# AnalogInput.net
KiCad netlist of a schematic drawn in Altium Designer
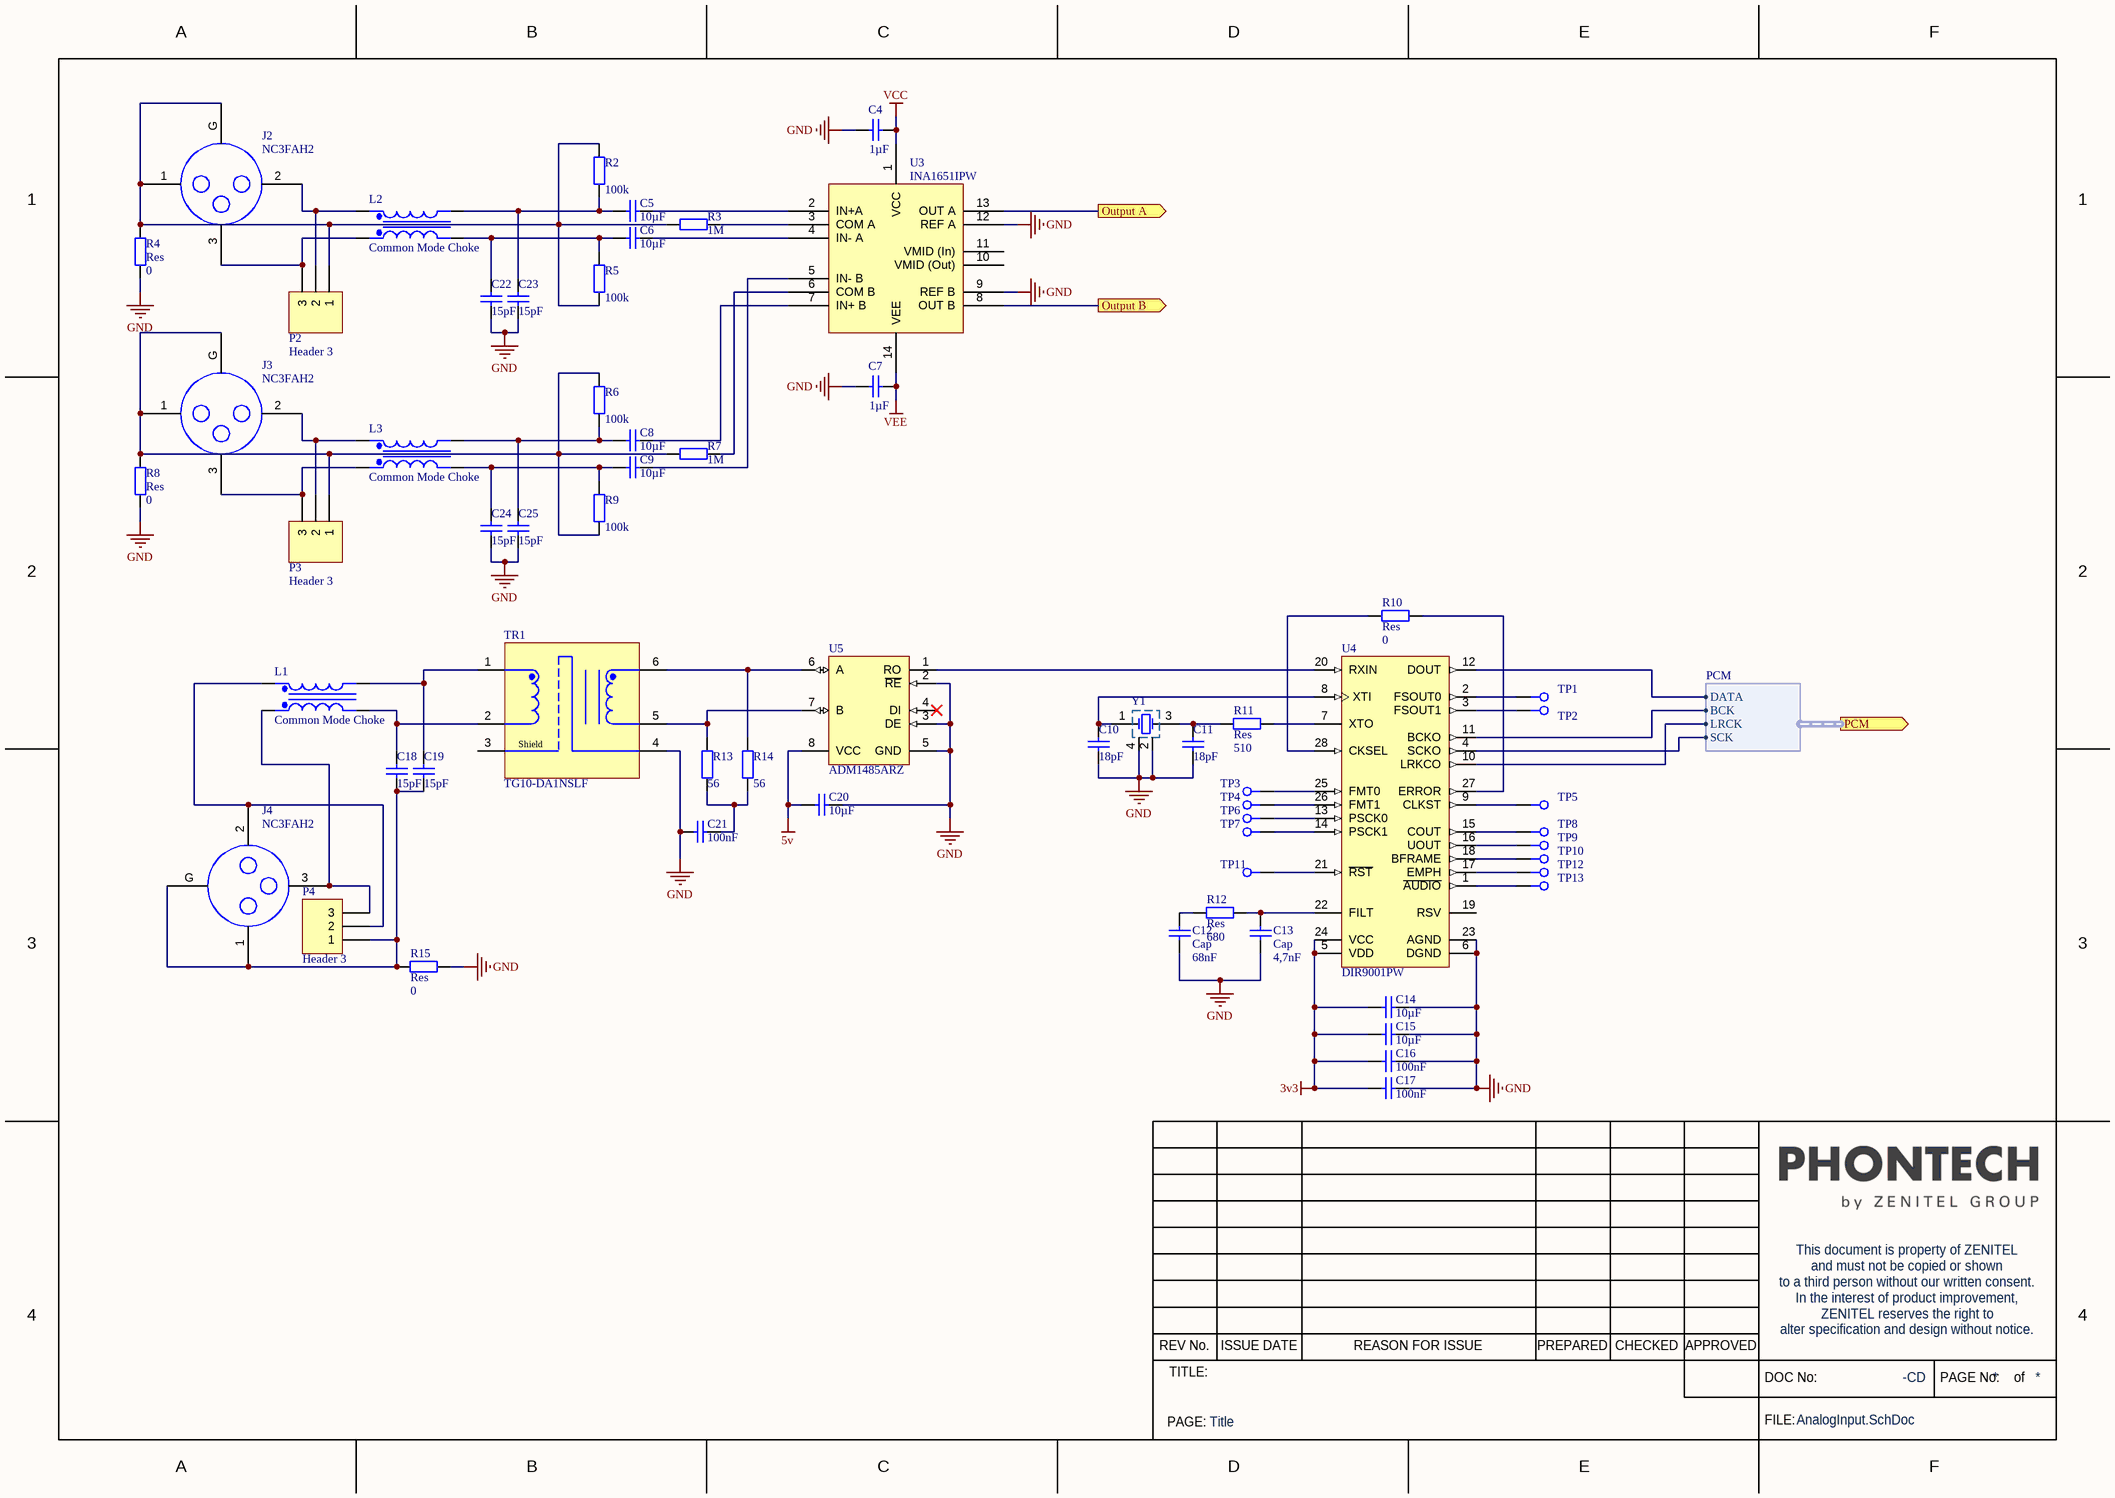
[diagram p0: AnalogInput.SchDoc]

(export (version "E")
  (design (tool "Eeschema 10.0.6"))
  (components
    (comp (ref "C4")
      (value "1µF")
      (footprint "CAPC3225N")
      (description "Chip cap 1uF 50v X7R 1210")
      (fields (field (name "TOLERANCE") "10%") (field (name "ZENITEL PARTNUMBER") "4000084277"))
      (libsource (lib "Zenitel Concord PRO Vault") (part "Capacitor-IEC"))
    )
    (comp (ref "C5")
      (value "10µF")
      (footprint "CAPC5750N")
      (description "10UF, 100V, X7S, 2220")
      (fields (field (name "TOLERANCE") "100%") (field (name "VOLTAGE") "100V"))
      (libsource (lib "Zenitel Concord PRO Vault") (part "Capacitor-IEC"))
    )
    (comp (ref "C6")
      (value "10µF")
      (footprint "CAPC5750N")
      (description "10UF, 100V, X7S, 2220")
      (fields (field (name "TOLERANCE") "100%") (field (name "VOLTAGE") "100V"))
      (libsource (lib "Zenitel Concord PRO Vault") (part "Capacitor-IEC"))
    )
    (comp (ref "C7")
      (value "1µF")
      (footprint "CAPC3225N")
      (description "Chip cap 1uF 50v X7R 1210")
      (fields (field (name "TOLERANCE") "10%") (field (name "ZENITEL PARTNUMBER") "4000084277"))
      (libsource (lib "Zenitel Concord PRO Vault") (part "Capacitor-IEC"))
    )
    (comp (ref "C8")
      (value "10µF")
      (footprint "CAPC5750N")
      (description "10UF, 100V, X7S, 2220")
      (fields (field (name "TOLERANCE") "100%") (field (name "VOLTAGE") "100V"))
      (libsource (lib "Zenitel Concord PRO Vault") (part "Capacitor-IEC"))
    )
    (comp (ref "C9")
      (value "10µF")
      (footprint "CAPC5750N")
      (description "10UF, 100V, X7S, 2220")
      (fields (field (name "TOLERANCE") "100%") (field (name "VOLTAGE") "100V"))
      (libsource (lib "Zenitel Concord PRO Vault") (part "Capacitor-IEC"))
    )
    (comp (ref "C10")
      (value "18pF")
      (footprint "CAPC1005X56X25NL10T15")
      (description "Chip cap 18p 50V - 0402")
      (fields (field (name "TOLERANCE") "5%") (field (name "ZENITEL PARTNUMBER") "4000080916"))
      (libsource (lib "Zenitel Concord PRO Vault") (part "Capacitor-IEC"))
    )
    (comp (ref "C11")
      (value "18pF")
      (footprint "CAPC1005X56X25NL10T15")
      (description "Chip cap 18p 50V - 0402")
      (fields (field (name "TOLERANCE") "5%") (field (name "ZENITEL PARTNUMBER") "4000080916"))
      (libsource (lib "Zenitel Concord PRO Vault") (part "Capacitor-IEC"))
    )
    (comp (ref "C12")
      (value "Cap")
      (footprint "CAPC1005X56X25ML10T15")
      (description "Chip cap 68n 10V - 0402")
      (fields
        (field (name "ALTIUM_VALUE") "68nF")
        (field (name "VOLTAGE") "10V")
        (field (name "TOLERANCE") "100%")
      )
      (libsource (lib "Zenitel Concord PRO Vault") (part "Capacitor-IEC"))
    )
    (comp (ref "C13")
      (value "Cap")
      (footprint "CAPC1005X56X25LL10T15")
      (description "Chip cap 4700p 50V - 0402")
      (fields
        (field (name "ALTIUM_VALUE") "4,7nF")
        (field (name "ZENITEL PARTNUMBER") "4000080940")
        (field (name "VOLTAGE") "50V")
      )
      (libsource (lib "Zenitel Concord PRO Vault") (part "Capacitor-IEC"))
    )
    (comp (ref "C14")
      (value "10µF")
      (footprint "CAPC2013X140X50LL20T25")
      (description "CR0805 10u 10V X7R 10% h=1.25mm")
      (fields (field (name "TOLERANCE") "10%") (field (name "VOLTAGE") "10V"))
      (libsource (lib "Zenitel Concord PRO Vault") (part "Capacitor-IEC"))
    )
    (comp (ref "C15")
      (value "10µF")
      (footprint "CAPC2013X140X50LL20T25")
      (description "CR0805 10u 10V X7R 10% h=1.25mm")
      (fields (field (name "TOLERANCE") "10%") (field (name "VOLTAGE") "10V"))
      (libsource (lib "Zenitel Concord PRO Vault") (part "Capacitor-IEC"))
    )
    (comp (ref "C16")
      (value "100nF")
      (footprint "CAPC1005X56X25NL10T15")
      (description "Chip cap  100n 10V - 0402  X7R")
      (fields (field (name "TOLERANCE") "10%") (field (name "VOLTAGE") "10V"))
      (libsource (lib "Zenitel Concord PRO Vault") (part "Capacitor-IEC"))
    )
    (comp (ref "C17")
      (value "100nF")
      (footprint "CAPC1005X56X25NL10T15")
      (description "Chip cap  100n 10V - 0402  X7R")
      (fields (field (name "TOLERANCE") "10%") (field (name "VOLTAGE") "10V"))
      (libsource (lib "Zenitel Concord PRO Vault") (part "Capacitor-IEC"))
    )
    (comp (ref "C18")
      (value "15pF")
      (footprint "CAPC1005X56X25NL10T15")
      (description "Chip cap 15pF 50V NP0 - 0402")
      (fields (field (name "TOLERANCE") "1%") (field (name "ZENITEL PARTNUMBER") "EFSMD17120"))
      (libsource (lib "Zenitel Concord PRO Vault") (part "Capacitor-IEC"))
    )
    (comp (ref "C19")
      (value "15pF")
      (footprint "CAPC1005X56X25NL10T15")
      (description "Chip cap 15pF 50V NP0 - 0402")
      (fields (field (name "TOLERANCE") "1%") (field (name "ZENITEL PARTNUMBER") "EFSMD17120"))
      (libsource (lib "Zenitel Concord PRO Vault") (part "Capacitor-IEC"))
    )
    (comp (ref "C20")
      (value "10µF")
      (footprint "CAPC2013X140X50LL20T25")
      (description "CR0805 10u 10V X7R 10% h=1.25mm")
      (fields (field (name "TOLERANCE") "10%") (field (name "VOLTAGE") "10V"))
      (libsource (lib "Zenitel Concord PRO Vault") (part "Capacitor-IEC"))
    )
    (comp (ref "C21")
      (value "100nF")
      (footprint "CAPC1608X90X35ML15T15")
      (description "Chip cap  100n 50V X7R - 0603")
      (fields (field (name "ZENITEL PARTNUMBER") "4000084734") (field (name "TOLERANCE") "10%"))
      (libsource (lib "Zenitel Concord PRO Vault") (part "Capacitor-IEC"))
    )
    (comp (ref "C22")
      (value "15pF")
      (footprint "CAPC1005X56X25NL10T15")
      (description "Chip cap 15pF 50V NP0 - 0402")
      (fields (field (name "TOLERANCE") "1%") (field (name "ZENITEL PARTNUMBER") "EFSMD17120"))
      (libsource (lib "Zenitel Concord PRO Vault") (part "Capacitor-IEC"))
    )
    (comp (ref "C23")
      (value "15pF")
      (footprint "CAPC1005X56X25NL10T15")
      (description "Chip cap 15pF 50V NP0 - 0402")
      (fields (field (name "TOLERANCE") "1%") (field (name "ZENITEL PARTNUMBER") "EFSMD17120"))
      (libsource (lib "Zenitel Concord PRO Vault") (part "Capacitor-IEC"))
    )
    (comp (ref "C24")
      (value "15pF")
      (footprint "CAPC1005X56X25NL10T15")
      (description "Chip cap 15pF 50V NP0 - 0402")
      (fields (field (name "TOLERANCE") "1%") (field (name "ZENITEL PARTNUMBER") "EFSMD17120"))
      (libsource (lib "Zenitel Concord PRO Vault") (part "Capacitor-IEC"))
    )
    (comp (ref "C25")
      (value "15pF")
      (footprint "CAPC1005X56X25NL10T15")
      (description "Chip cap 15pF 50V NP0 - 0402")
      (fields (field (name "TOLERANCE") "1%") (field (name "ZENITEL PARTNUMBER") "EFSMD17120"))
      (libsource (lib "Zenitel Concord PRO Vault") (part "Capacitor-IEC"))
    )
    (comp (ref "J2")
      (value "NC3FAH2")
      (footprint "NC3FAH2")
      (description "NC3FAH2 3pole female XLR 90deg")
      (fields (field (name "ZENITEL PARTNUMBER") "4000083398"))
      (libsource (lib "Zenitel Concord PRO Vault") (part "NC3FAH2"))
    )
    (comp (ref "J3")
      (value "NC3FAH2")
      (footprint "NC3FAH2")
      (description "NC3FAH2 3pole female XLR 90deg")
      (fields (field (name "ZENITEL PARTNUMBER") "4000083398"))
      (libsource (lib "Zenitel Concord PRO Vault") (part "NC3FAH2"))
    )
    (comp (ref "J4")
      (value "NC3FAH2")
      (footprint "NC3FAH2")
      (description "NC3FAH2 3pole female XLR 90deg")
      (fields (field (name "ZENITEL PARTNUMBER") "4000083398"))
      (libsource (lib "Zenitel Concord PRO Vault") (part "NC3FAH2"))
    )
    (comp (ref "L1")
      (value "Common Mode Choke")
      (footprint "WE-CNSW-1206")
      (description "WE-CNSW SMD Common Mode Line Filter")
      (fields (field (name "ZENITEL PARTNUMBER") "4000086128"))
      (libsource (lib "Zenitel Concord PRO Vault") (part "Common Mode Choke"))
    )
    (comp (ref "L2")
      (value "Common Mode Choke")
      (footprint "WE-CNSW-1206")
      (description "WE-CNSW SMD Common Mode Line Filter")
      (fields (field (name "ZENITEL PARTNUMBER") "4000086128"))
      (libsource (lib "Zenitel Concord PRO Vault") (part "Common Mode Choke"))
    )
    (comp (ref "L3")
      (value "Common Mode Choke")
      (footprint "WE-CNSW-1206")
      (description "WE-CNSW SMD Common Mode Line Filter")
      (fields (field (name "ZENITEL PARTNUMBER") "4000086128"))
      (libsource (lib "Zenitel Concord PRO Vault") (part "Common Mode Choke"))
    )
    (comp (ref "P2")
      (value "Header 3")
      (footprint "MTA-100-3P")
      (description "MTA-100-3P 3-pin header")
      (fields (field (name "ZENITEL PARTNUMBER") "4000085467"))
      (libsource (lib "Zenitel Concord PRO Vault") (part "Header 3"))
    )
    (comp (ref "P3")
      (value "Header 3")
      (footprint "MTA-100-3P")
      (description "MTA-100-3P 3-pin header")
      (fields (field (name "ZENITEL PARTNUMBER") "4000085467"))
      (libsource (lib "Zenitel Concord PRO Vault") (part "Header 3"))
    )
    (comp (ref "P4")
      (value "Header 3")
      (footprint "MTA-100-3P")
      (description "MTA-100-3P 3-pin header")
      (fields (field (name "ZENITEL PARTNUMBER") "4000085467"))
      (libsource (lib "") (part "Header 3_1"))
    )
    (comp (ref "R2")
      (value "100k")
      (footprint "RESC1005X40X25NL05T05")
      (description "Chip resistor 100K - 0402")
      (fields (field (name "POWER") "62,5mW") (field (name "ZENITEL PARTNUMBER") "4000081112"))
      (libsource (lib "Zenitel Concord PRO Vault") (part "Resistor-IEC"))
    )
    (comp (ref "R3")
      (value "1M")
      (footprint "RESC1005X40X25NL05T05")
      (description "Chip resistor 1M 1% - 0402")
      (fields (field (name "VOLTAGE") "50V") (field (name "POWER") "62,5mW"))
      (libsource (lib "") (part "Resistor-IEC_1"))
    )
    (comp (ref "R4")
      (value "Res")
      (footprint "RESC3216X60X45LL10T20")
      (description "0R 1206")
      (fields
        (field (name "ALTIUM_VALUE") "0")
        (field (name "ZENITEL PARTNUMBER") "4000085059")
        (field (name "POWER") "250mW")
      )
      (libsource (lib "Zenitel Concord PRO Vault") (part "Resistor-IEC"))
    )
    (comp (ref "R5")
      (value "100k")
      (footprint "RESC1005X40X25NL05T05")
      (description "Chip resistor 100K - 0402")
      (fields (field (name "POWER") "62,5mW") (field (name "ZENITEL PARTNUMBER") "4000081112"))
      (libsource (lib "Zenitel Concord PRO Vault") (part "Resistor-IEC"))
    )
    (comp (ref "R6")
      (value "100k")
      (footprint "RESC1005X40X25NL05T05")
      (description "Chip resistor 100K - 0402")
      (fields (field (name "POWER") "62,5mW") (field (name "ZENITEL PARTNUMBER") "4000081112"))
      (libsource (lib "Zenitel Concord PRO Vault") (part "Resistor-IEC"))
    )
    (comp (ref "R7")
      (value "1M")
      (footprint "RESC1005X40X25NL05T05")
      (description "Chip resistor 1M 1% - 0402")
      (fields (field (name "VOLTAGE") "50V") (field (name "POWER") "62,5mW"))
      (libsource (lib "") (part "Resistor-IEC_1"))
    )
    (comp (ref "R8")
      (value "Res")
      (footprint "RESC3216X60X45LL10T20")
      (description "0R 1206")
      (fields
        (field (name "ALTIUM_VALUE") "0")
        (field (name "ZENITEL PARTNUMBER") "4000085059")
        (field (name "POWER") "250mW")
      )
      (libsource (lib "Zenitel Concord PRO Vault") (part "Resistor-IEC"))
    )
    (comp (ref "R9")
      (value "100k")
      (footprint "RESC1005X40X25NL05T05")
      (description "Chip resistor 100K - 0402")
      (fields (field (name "POWER") "62,5mW") (field (name "ZENITEL PARTNUMBER") "4000081112"))
      (libsource (lib "Zenitel Concord PRO Vault") (part "Resistor-IEC"))
    )
    (comp (ref "R10")
      (value "Res")
      (footprint "RESC1005X40X25NL05T05")
      (description "Chip resistor 0R - 0402")
      (fields
        (field (name "ALTIUM_VALUE") "0")
        (field (name "POWER") "62,5mW")
        (field (name "TOLERANCE") "1%")
      )
      (libsource (lib "") (part "Resistor-IEC_1"))
    )
    (comp (ref "R11")
      (value "Res")
      (footprint "RESC1005X40X25NL05T05")
      (description "Chip resistor 0402 - 510R 1%")
      (fields
        (field (name "ALTIUM_VALUE") "510")
        (field (name "TOLERANCE") "1%")
        (field (name "ZENITEL PARTNUMBER") "4000088250")
      )
      (libsource (lib "") (part "Resistor-IEC_1"))
    )
    (comp (ref "R12")
      (value "Res")
      (footprint "RESC1005X40X25NL05T05")
      (description "Chip resistor 680R - 0402")
      (fields
        (field (name "ALTIUM_VALUE") "680")
        (field (name "POWER") "62,5mW")
        (field (name "TOLERANCE") "1%")
      )
      (libsource (lib "") (part "Resistor-IEC_1"))
    )
    (comp (ref "R13")
      (value "56")
      (footprint "RESC1609X50X30ML10T20")
      (description "CR 0603 56R 5%")
      (fields (field (name "ZENITEL PARTNUMBER") "4000098393") (field (name "POWER") "100mW"))
      (libsource (lib "Zenitel Concord PRO Vault") (part "Resistor-IEC"))
    )
    (comp (ref "R14")
      (value "56")
      (footprint "RESC1609X50X30ML10T20")
      (description "CR 0603 56R 5%")
      (fields (field (name "ZENITEL PARTNUMBER") "4000098393") (field (name "POWER") "100mW"))
      (libsource (lib "Zenitel Concord PRO Vault") (part "Resistor-IEC"))
    )
    (comp (ref "R15")
      (value "Res")
      (footprint "RESC3216X60X45LL10T20")
      (description "0R 1206")
      (fields
        (field (name "ALTIUM_VALUE") "0")
        (field (name "ZENITEL PARTNUMBER") "4000085059")
        (field (name "POWER") "250mW")
      )
      (libsource (lib "") (part "Resistor-IEC_2"))
    )
    (comp (ref "TP1")
      (value "TP Ø1.27MM")
      (footprint "TP_1.27MM")
      (description "Test Point, copper pad, 1.27mm diameter")
      (libsource (lib "Zenitel Concord PRO Vault") (part "Symbol"))
    )
    (comp (ref "TP2")
      (value "TP Ø1.27MM")
      (footprint "TP_1.27MM")
      (description "Test Point, copper pad, 1.27mm diameter")
      (libsource (lib "Zenitel Concord PRO Vault") (part "Symbol"))
    )
    (comp (ref "TP3")
      (value "TP Ø1.27MM")
      (footprint "TP_1.27MM")
      (description "Test Point, copper pad, 1.27mm diameter")
      (libsource (lib "Zenitel Concord PRO Vault") (part "Symbol"))
    )
    (comp (ref "TP4")
      (value "TP Ø1.27MM")
      (footprint "TP_1.27MM")
      (description "Test Point, copper pad, 1.27mm diameter")
      (libsource (lib "Zenitel Concord PRO Vault") (part "Symbol"))
    )
    (comp (ref "TP5")
      (value "TP Ø1.27MM")
      (footprint "TP_1.27MM")
      (description "Test Point, copper pad, 1.27mm diameter")
      (libsource (lib "Zenitel Concord PRO Vault") (part "Symbol"))
    )
    (comp (ref "TP6")
      (value "TP Ø1.27MM")
      (footprint "TP_1.27MM")
      (description "Test Point, copper pad, 1.27mm diameter")
      (libsource (lib "Zenitel Concord PRO Vault") (part "Symbol"))
    )
    (comp (ref "TP7")
      (value "TP Ø1.27MM")
      (footprint "TP_1.27MM")
      (description "Test Point, copper pad, 1.27mm diameter")
      (libsource (lib "Zenitel Concord PRO Vault") (part "Symbol"))
    )
    (comp (ref "TP8")
      (value "TP Ø1.27MM")
      (footprint "TP_1.27MM")
      (description "Test Point, copper pad, 1.27mm diameter")
      (libsource (lib "Zenitel Concord PRO Vault") (part "Symbol"))
    )
    (comp (ref "TP9")
      (value "TP Ø1.27MM")
      (footprint "TP_1.27MM")
      (description "Test Point, copper pad, 1.27mm diameter")
      (libsource (lib "Zenitel Concord PRO Vault") (part "Symbol"))
    )
    (comp (ref "TP10")
      (value "TP Ø1.27MM")
      (footprint "TP_1.27MM")
      (description "Test Point, copper pad, 1.27mm diameter")
      (libsource (lib "Zenitel Concord PRO Vault") (part "Symbol"))
    )
    (comp (ref "TP11")
      (value "TP Ø1.27MM")
      (footprint "TP_1.27MM")
      (description "Test Point, copper pad, 1.27mm diameter")
      (libsource (lib "Zenitel Concord PRO Vault") (part "Symbol"))
    )
    (comp (ref "TP12")
      (value "TP Ø1.27MM")
      (footprint "TP_1.27MM")
      (description "Test Point, copper pad, 1.27mm diameter")
      (libsource (lib "Zenitel Concord PRO Vault") (part "Symbol"))
    )
    (comp (ref "TP13")
      (value "TP Ø1.27MM")
      (footprint "TP_1.27MM")
      (description "Test Point, copper pad, 1.27mm diameter")
      (libsource (lib "Zenitel Concord PRO Vault") (part "Symbol"))
    )
    (comp (ref "TR1")
      (value "TG10-DA1NSLF")
      (footprint "TG10-DA1NSLF-Footprint-1")
      (description "Audio Transformers / Signal Transformers ISO MOD GullWng Sgl Audio w/ shield 6pin")
      (libsource (lib "Zenitel Concord PRO Vault") (part "TG10-DA1NSLF"))
    )
    (comp (ref "U3")
      (value "INA1651IPW")
      (footprint "SOP65P640X120-14N")
      (description "SoundPlus™ high common-mode rejection (91-dB), low THD+N (-120-dB) dual differential line receiver")
      (libsource (lib "Zenitel Concord PRO Vault") (part "INA1651IPW"))
    )
    (comp (ref "U4")
      (value "DIR9001PW")
      (footprint "PW0028A_N")
      (fields (field (name "MANUFACTURER") "Texas Instruments"))
      (libsource (lib "Altium Content Vault") (part "TI-DIR9001-TSSOP_PW-28"))
    )
    (comp (ref "U5")
      (value "ADM1485ARZ")
      (footprint "ADI-R-8_M")
      (fields (field (name "MANUFACTURER") "Analog Devices"))
      (libsource (lib "Altium Content Vault") (part "ADI-ADM3483_5-R-8"))
    )
    (comp (ref "Y1")
      (value "Crystal4")
      (footprint "XTAL-5x3.2MM")
      (description "Crystal 24.576MHZ 18pF 5X3.2mm")
      (fields (field (name "ZENITEL PARTNUMBER") "4000086516"))
      (libsource (lib "Zenitel Concord PRO Vault") (part "Crystal4"))
    )
  )
  (nets
    (net (code "2") (name "/BCK") (class "Default")
      (node (ref "U4") (pin "11") (pinfunction "BCKO_11") (pintype "output"))
    )
    (net (code "3") (name "/DATA") (class "Default")
      (node (ref "U4") (pin "12") (pinfunction "DOUT_12") (pintype "output"))
    )
    (net (code "4") (name "/LRCK") (class "Default")
      (node (ref "U4") (pin "10") (pinfunction "LRKCO_10") (pintype "output"))
    )
    (net (code "5") (name "/Output A") (class "Default")
      (node (ref "U3") (pin "13") (pinfunction "OUT_A_13") (pintype "passive"))
    )
    (net (code "6") (name "/Output B") (class "Default")
      (node (ref "U3") (pin "8") (pinfunction "OUT_B_8") (pintype "passive"))
    )
    (net (code "7") (name "/SCK") (class "Default")
      (node (ref "U4") (pin "4") (pinfunction "SCKO_4") (pintype "output"))
    )
    (net (code "9") (name "3v3") (class "Default")
      (node (ref "C14") (pin "2") (pinfunction "2_2") (pintype "passive"))
      (node (ref "C15") (pin "2") (pinfunction "2_2") (pintype "passive"))
      (node (ref "C16") (pin "1") (pinfunction "1_1") (pintype "passive"))
      (node (ref "C17") (pin "1") (pinfunction "1_1") (pintype "passive"))
      (node (ref "U4") (pin "24") (pinfunction "VCC_24") (pintype "power_in"))
      (node (ref "U4") (pin "5") (pinfunction "VDD_5") (pintype "power_in"))
    )
    (net (code "10") (name "5v") (class "Default")
      (node (ref "C20") (pin "2") (pinfunction "2_2") (pintype "passive"))
      (node (ref "U5") (pin "8") (pinfunction "VCC_8") (pintype "power_in"))
    )
    (net (code "11") (name "GND") (class "Default")
      (node (ref "C10") (pin "1") (pinfunction "1_1") (pintype "passive"))
      (node (ref "C11") (pin "1") (pinfunction "1_1") (pintype "passive"))
      (node (ref "C12") (pin "1") (pinfunction "1_1") (pintype "passive"))
      (node (ref "C13") (pin "1") (pinfunction "1_1") (pintype "passive"))
      (node (ref "C14") (pin "1") (pinfunction "1_1") (pintype "passive"))
      (node (ref "C15") (pin "1") (pinfunction "1_1") (pintype "passive"))
      (node (ref "C16") (pin "2") (pinfunction "2_2") (pintype "passive"))
      (node (ref "C17") (pin "2") (pinfunction "2_2") (pintype "passive"))
      (node (ref "C20") (pin "1") (pinfunction "1_1") (pintype "passive"))
      (node (ref "C21") (pin "1") (pinfunction "1_1") (pintype "passive"))
      (node (ref "C22") (pin "1") (pinfunction "1_1") (pintype "passive"))
      (node (ref "C23") (pin "1") (pinfunction "1_1") (pintype "passive"))
      (node (ref "C24") (pin "1") (pinfunction "1_1") (pintype "passive"))
      (node (ref "C25") (pin "1") (pinfunction "1_1") (pintype "passive"))
      (node (ref "C4") (pin "1") (pinfunction "1_1") (pintype "passive"))
      (node (ref "C7") (pin "1") (pinfunction "1_1") (pintype "passive"))
      (node (ref "R15") (pin "1") (pinfunction "1_1") (pintype "passive"))
      (node (ref "R4") (pin "1") (pinfunction "1_1") (pintype "passive"))
      (node (ref "R8") (pin "1") (pinfunction "1_1") (pintype "passive"))
      (node (ref "TR1") (pin "4") (pinfunction "4_4") (pintype "passive"))
      (node (ref "U3") (pin "12") (pinfunction "REF_A_12") (pintype "passive"))
      (node (ref "U3") (pin "9") (pinfunction "REF_B_9") (pintype "passive"))
      (node (ref "U4") (pin "23") (pinfunction "AGND_23") (pintype "power_in"))
      (node (ref "U4") (pin "6") (pinfunction "DGND_6") (pintype "power_in"))
      (node (ref "U5") (pin "2") (pinfunction "~{RE}_2") (pintype "input"))
      (node (ref "U5") (pin "3") (pinfunction "DE_3") (pintype "input"))
      (node (ref "U5") (pin "5") (pinfunction "GND_5") (pintype "power_in"))
      (node (ref "Y1") (pin "2") (pinfunction "GND_2") (pintype "power_in"))
      (node (ref "Y1") (pin "4") (pinfunction "4_4") (pintype "passive"))
    )
    (net (code "12") (name "Net-(C12-Pad2)") (class "Default")
      (node (ref "C12") (pin "2") (pinfunction "2_2") (pintype "passive"))
      (node (ref "R12") (pin "1") (pinfunction "1_1") (pintype "passive"))
    )
    (net (code "13") (name "Net-(C18-Pad1)") (class "Default")
      (node (ref "C18") (pin "1") (pinfunction "1_1") (pintype "passive"))
      (node (ref "C19") (pin "1") (pinfunction "1_1") (pintype "passive"))
      (node (ref "J4") (pin "1") (pinfunction "1_1") (pintype "passive"))
      (node (ref "J4") (pin "G") (pinfunction "G_G") (pintype "passive"))
      (node (ref "P4") (pin "1") (pinfunction "1_1") (pintype "passive"))
      (node (ref "R15") (pin "2") (pinfunction "2_2") (pintype "passive"))
    )
    (net (code "14") (name "Net-(C18-Pad2)") (class "Default")
      (node (ref "C18") (pin "2") (pinfunction "2_2") (pintype "passive"))
      (node (ref "L1") (pin "4") (pinfunction "4_4") (pintype "passive"))
      (node (ref "TR1") (pin "2") (pinfunction "2_2") (pintype "passive"))
    )
    (net (code "15") (name "Net-(C19-Pad2)") (class "Default")
      (node (ref "C19") (pin "2") (pinfunction "2_2") (pintype "passive"))
      (node (ref "L1") (pin "3") (pinfunction "3_3") (pintype "passive"))
      (node (ref "TR1") (pin "1") (pinfunction "1_1") (pintype "passive"))
    )
    (net (code "16") (name "Net-(C21-Pad2)") (class "Default")
      (node (ref "C21") (pin "2") (pinfunction "2_2") (pintype "passive"))
      (node (ref "R13") (pin "1") (pinfunction "1_1") (pintype "passive"))
      (node (ref "R14") (pin "1") (pinfunction "1_1") (pintype "passive"))
    )
    (net (code "17") (name "Net-(C22-Pad2)") (class "Default")
      (node (ref "C22") (pin "2") (pinfunction "2_2") (pintype "passive"))
      (node (ref "C6") (pin "1") (pinfunction "1_1") (pintype "passive"))
      (node (ref "L2") (pin "4") (pinfunction "4_4") (pintype "passive"))
      (node (ref "R5") (pin "2") (pinfunction "2_2") (pintype "passive"))
    )
    (net (code "18") (name "Net-(C23-Pad2)") (class "Default")
      (node (ref "C23") (pin "2") (pinfunction "2_2") (pintype "passive"))
      (node (ref "C5") (pin "1") (pinfunction "1_1") (pintype "passive"))
      (node (ref "L2") (pin "3") (pinfunction "3_3") (pintype "passive"))
      (node (ref "R2") (pin "1") (pinfunction "1_1") (pintype "passive"))
    )
    (net (code "19") (name "Net-(C24-Pad2)") (class "Default")
      (node (ref "C24") (pin "2") (pinfunction "2_2") (pintype "passive"))
      (node (ref "C9") (pin "1") (pinfunction "1_1") (pintype "passive"))
      (node (ref "L3") (pin "4") (pinfunction "4_4") (pintype "passive"))
      (node (ref "R9") (pin "2") (pinfunction "2_2") (pintype "passive"))
    )
    (net (code "20") (name "Net-(C25-Pad2)") (class "Default")
      (node (ref "C25") (pin "2") (pinfunction "2_2") (pintype "passive"))
      (node (ref "C8") (pin "1") (pinfunction "1_1") (pintype "passive"))
      (node (ref "L3") (pin "3") (pinfunction "3_3") (pintype "passive"))
      (node (ref "R6") (pin "1") (pinfunction "1_1") (pintype "passive"))
    )
    (net (code "21") (name "Net-(J2-Pad1)") (class "Default")
      (node (ref "J2") (pin "1") (pinfunction "1_1") (pintype "passive"))
      (node (ref "J2") (pin "G") (pinfunction "G_G") (pintype "passive"))
      (node (ref "P2") (pin "1") (pinfunction "1_1") (pintype "passive"))
      (node (ref "R2") (pin "2") (pinfunction "2_2") (pintype "passive"))
      (node (ref "R3") (pin "1") (pinfunction "1_1") (pintype "passive"))
      (node (ref "R4") (pin "2") (pinfunction "2_2") (pintype "passive"))
      (node (ref "R5") (pin "1") (pinfunction "1_1") (pintype "passive"))
    )
    (net (code "22") (name "Net-(J2-Pad2)") (class "Default")
      (node (ref "J2") (pin "2") (pinfunction "2_2") (pintype "passive"))
      (node (ref "L2") (pin "2") (pinfunction "2_2") (pintype "passive"))
      (node (ref "P2") (pin "2") (pinfunction "2_2") (pintype "passive"))
    )
    (net (code "23") (name "Net-(J2-Pad3)") (class "Default")
      (node (ref "J2") (pin "3") (pinfunction "3_3") (pintype "passive"))
      (node (ref "L2") (pin "1") (pinfunction "1_1") (pintype "passive"))
      (node (ref "P2") (pin "3") (pinfunction "3_3") (pintype "passive"))
    )
    (net (code "24") (name "Net-(J3-Pad1)") (class "Default")
      (node (ref "J3") (pin "1") (pinfunction "1_1") (pintype "passive"))
      (node (ref "J3") (pin "G") (pinfunction "G_G") (pintype "passive"))
      (node (ref "P3") (pin "1") (pinfunction "1_1") (pintype "passive"))
      (node (ref "R6") (pin "2") (pinfunction "2_2") (pintype "passive"))
      (node (ref "R7") (pin "1") (pinfunction "1_1") (pintype "passive"))
      (node (ref "R8") (pin "2") (pinfunction "2_2") (pintype "passive"))
      (node (ref "R9") (pin "1") (pinfunction "1_1") (pintype "passive"))
    )
    (net (code "25") (name "Net-(J3-Pad2)") (class "Default")
      (node (ref "J3") (pin "2") (pinfunction "2_2") (pintype "passive"))
      (node (ref "L3") (pin "2") (pinfunction "2_2") (pintype "passive"))
      (node (ref "P3") (pin "2") (pinfunction "2_2") (pintype "passive"))
    )
    (net (code "26") (name "Net-(J3-Pad3)") (class "Default")
      (node (ref "J3") (pin "3") (pinfunction "3_3") (pintype "passive"))
      (node (ref "L3") (pin "1") (pinfunction "1_1") (pintype "passive"))
      (node (ref "P3") (pin "3") (pinfunction "3_3") (pintype "passive"))
    )
    (net (code "27") (name "Net-(J4-Pad2)") (class "Default")
      (node (ref "J4") (pin "2") (pinfunction "2_2") (pintype "passive"))
      (node (ref "L1") (pin "2") (pinfunction "2_2") (pintype "passive"))
      (node (ref "P4") (pin "2") (pinfunction "2_2") (pintype "passive"))
    )
    (net (code "28") (name "Net-(J4-Pad3)") (class "Default")
      (node (ref "J4") (pin "3") (pinfunction "3_3") (pintype "passive"))
      (node (ref "L1") (pin "1") (pinfunction "1_1") (pintype "passive"))
      (node (ref "P4") (pin "3") (pinfunction "3_3") (pintype "passive"))
    )
    (net (code "29") (name "Net-(U3-COM_A)") (class "Default")
      (node (ref "R3") (pin "2") (pinfunction "2_2") (pintype "passive"))
      (node (ref "U3") (pin "3") (pinfunction "COM_A_3") (pintype "passive"))
    )
    (net (code "30") (name "Net-(U3-COM_B)") (class "Default")
      (node (ref "R7") (pin "2") (pinfunction "2_2") (pintype "passive"))
      (node (ref "U3") (pin "6") (pinfunction "COM_B_6") (pintype "passive"))
    )
    (net (code "31") (name "Net-(U3-IN+A)") (class "Default")
      (node (ref "C5") (pin "2") (pinfunction "2_2") (pintype "passive"))
      (node (ref "U3") (pin "2") (pinfunction "IN+A_2") (pintype "passive"))
    )
    (net (code "32") (name "Net-(U3-IN+_B)") (class "Default")
      (node (ref "C8") (pin "2") (pinfunction "2_2") (pintype "passive"))
      (node (ref "U3") (pin "7") (pinfunction "IN+_B_7") (pintype "passive"))
    )
    (net (code "33") (name "Net-(U3-IN-_A)") (class "Default")
      (node (ref "C6") (pin "2") (pinfunction "2_2") (pintype "passive"))
      (node (ref "U3") (pin "4") (pinfunction "IN-_A_4") (pintype "passive"))
    )
    (net (code "34") (name "Net-(U3-IN-_B)") (class "Default")
      (node (ref "C9") (pin "2") (pinfunction "2_2") (pintype "passive"))
      (node (ref "U3") (pin "5") (pinfunction "IN-_B_5") (pintype "passive"))
    )
    (net (code "35") (name "Net-(U4-BFRAME)") (class "Default")
      (node (ref "TP10") (pin "1") (pinfunction "1_1") (pintype "passive"))
      (node (ref "U4") (pin "18") (pinfunction "BFRAME_18") (pintype "output"))
    )
    (net (code "36") (name "Net-(U4-CKSEL)") (class "Default")
      (node (ref "R10") (pin "1") (pinfunction "1_1") (pintype "passive"))
      (node (ref "U4") (pin "28") (pinfunction "CKSEL_28") (pintype "input"))
    )
    (net (code "37") (name "Net-(U4-CLKST)") (class "Default")
      (node (ref "TP5") (pin "1") (pinfunction "1_1") (pintype "passive"))
      (node (ref "U4") (pin "9") (pinfunction "CLKST_9") (pintype "output"))
    )
    (net (code "38") (name "Net-(U4-COUT)") (class "Default")
      (node (ref "TP8") (pin "1") (pinfunction "1_1") (pintype "passive"))
      (node (ref "U4") (pin "15") (pinfunction "COUT_15") (pintype "output"))
    )
    (net (code "39") (name "Net-(U4-EMPH)") (class "Default")
      (node (ref "TP12") (pin "1") (pinfunction "1_1") (pintype "passive"))
      (node (ref "U4") (pin "17") (pinfunction "EMPH_17") (pintype "output"))
    )
    (net (code "40") (name "Net-(U4-ERROR)") (class "Default")
      (node (ref "R10") (pin "2") (pinfunction "2_2") (pintype "passive"))
      (node (ref "U4") (pin "27") (pinfunction "ERROR_27") (pintype "output"))
    )
    (net (code "41") (name "Net-(U4-FILT)") (class "Default")
      (node (ref "C13") (pin "2") (pinfunction "2_2") (pintype "passive"))
      (node (ref "R12") (pin "2") (pinfunction "2_2") (pintype "passive"))
      (node (ref "U4") (pin "22") (pinfunction "FILT_22") (pintype "passive"))
    )
    (net (code "42") (name "Net-(U4-FMT0)") (class "Default")
      (node (ref "TP3") (pin "1") (pinfunction "1_1") (pintype "passive"))
      (node (ref "U4") (pin "25") (pinfunction "FMT0_25") (pintype "input"))
    )
    (net (code "43") (name "Net-(U4-FMT1)") (class "Default")
      (node (ref "TP4") (pin "1") (pinfunction "1_1") (pintype "passive"))
      (node (ref "U4") (pin "26") (pinfunction "FMT1_26") (pintype "input"))
    )
    (net (code "44") (name "Net-(U4-FSOUT0)") (class "Default")
      (node (ref "TP1") (pin "1") (pinfunction "1_1") (pintype "passive"))
      (node (ref "U4") (pin "2") (pinfunction "FSOUT0_2") (pintype "output"))
    )
    (net (code "45") (name "Net-(U4-FSOUT1)") (class "Default")
      (node (ref "TP2") (pin "1") (pinfunction "1_1") (pintype "passive"))
      (node (ref "U4") (pin "3") (pinfunction "FSOUT1_3") (pintype "output"))
    )
    (net (code "46") (name "Net-(U4-PSCK0)") (class "Default")
      (node (ref "TP6") (pin "1") (pinfunction "1_1") (pintype "passive"))
      (node (ref "U4") (pin "13") (pinfunction "PSCK0_13") (pintype "input"))
    )
    (net (code "47") (name "Net-(U4-PSCK1)") (class "Default")
      (node (ref "TP7") (pin "1") (pinfunction "1_1") (pintype "passive"))
      (node (ref "U4") (pin "14") (pinfunction "PSCK1_14") (pintype "input"))
    )
    (net (code "48") (name "Net-(U4-RXIN)") (class "Default")
      (node (ref "U4") (pin "20") (pinfunction "RXIN_20") (pintype "input"))
      (node (ref "U5") (pin "1") (pinfunction "RO_1") (pintype "tri_state"))
    )
    (net (code "49") (name "Net-(U4-UOUT)") (class "Default")
      (node (ref "TP9") (pin "1") (pinfunction "1_1") (pintype "passive"))
      (node (ref "U4") (pin "16") (pinfunction "UOUT_16") (pintype "output"))
    )
    (net (code "50") (name "Net-(U4-XTI)") (class "Default")
      (node (ref "C10") (pin "2") (pinfunction "2_2") (pintype "passive"))
      (node (ref "U4") (pin "8") (pinfunction "XTI_8") (pintype "input"))
      (node (ref "Y1") (pin "1") (pinfunction "OSC1_1") (pintype "passive"))
    )
    (net (code "51") (name "Net-(U4-XTO)") (class "Default")
      (node (ref "R11") (pin "2") (pinfunction "2_2") (pintype "passive"))
      (node (ref "U4") (pin "7") (pinfunction "XTO_7") (pintype "passive"))
    )
    (net (code "52") (name "Net-(U4-~{AUDIO})") (class "Default")
      (node (ref "TP13") (pin "1") (pinfunction "1_1") (pintype "passive"))
      (node (ref "U4") (pin "1") (pinfunction "~{AUDIO}_1") (pintype "output"))
    )
    (net (code "53") (name "Net-(U4-~{RST})") (class "Default")
      (node (ref "TP11") (pin "1") (pinfunction "1_1") (pintype "passive"))
      (node (ref "U4") (pin "21") (pinfunction "~{RST}_21") (pintype "input"))
    )
    (net (code "54") (name "Net-(U5-A)") (class "Default")
      (node (ref "R14") (pin "2") (pinfunction "2_2") (pintype "passive"))
      (node (ref "TR1") (pin "6") (pinfunction "6_6") (pintype "passive"))
      (node (ref "U5") (pin "6") (pinfunction "A_6") (pintype "bidirectional"))
    )
    (net (code "55") (name "Net-(U5-B)") (class "Default")
      (node (ref "R13") (pin "2") (pinfunction "2_2") (pintype "passive"))
      (node (ref "TR1") (pin "5") (pinfunction "5_5") (pintype "passive"))
      (node (ref "U5") (pin "7") (pinfunction "B_7") (pintype "bidirectional"))
    )
    (net (code "56") (name "Net-(Y1-OSC2)") (class "Default")
      (node (ref "C11") (pin "2") (pinfunction "2_2") (pintype "passive"))
      (node (ref "R11") (pin "1") (pinfunction "1_1") (pintype "passive"))
      (node (ref "Y1") (pin "3") (pinfunction "OSC2_3") (pintype "passive"))
    )
    (net (code "57") (name "VCC") (class "Default")
      (node (ref "C4") (pin "2") (pinfunction "2_2") (pintype "passive"))
      (node (ref "U3") (pin "1") (pinfunction "VCC_1") (pintype "passive"))
    )
    (net (code "58") (name "VEE") (class "Default")
      (node (ref "C7") (pin "2") (pinfunction "2_2") (pintype "passive"))
      (node (ref "U3") (pin "14") (pinfunction "VEE_14") (pintype "passive"))
    )
    (net (code "59") (name "unconnected-(TR1-Pad3)") (class "Default")
      (node (ref "TR1") (pin "3") (pinfunction "3_3") (pintype "passive"))
    )
    (net (code "60") (name "unconnected-(U3-VMID_(In)-Pad11)") (class "Default")
      (node (ref "U3") (pin "11") (pinfunction "VMID_(In)_11") (pintype "passive"))
    )
    (net (code "61") (name "unconnected-(U3-VMID_(Out)-Pad10)") (class "Default")
      (node (ref "U3") (pin "10") (pinfunction "VMID_(Out)_10") (pintype "passive"))
    )
    (net (code "62") (name "unconnected-(U4-RSV-Pad19)") (class "Default")
      (node (ref "U4") (pin "19") (pinfunction "RSV_19") (pintype "power_in"))
    )
    (net (code "63") (name "unconnected-(U5-DI-Pad4)") (class "Default")
      (node (ref "U5") (pin "4") (pinfunction "DI_4") (pintype "input+no_connect"))
    )
  )
)
